# Current_Sensor.net
KiCad netlist of a schematic drawn in Altium Designer
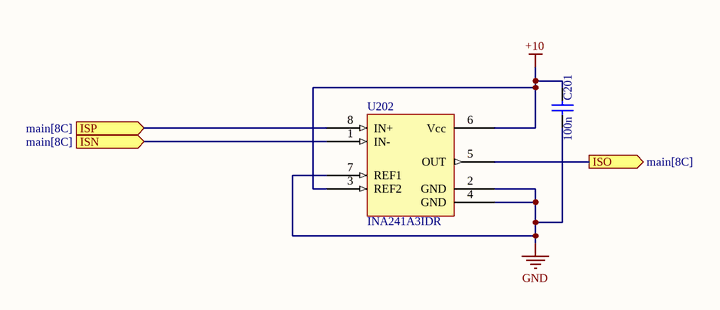
[diagram p0: Current_Sensor.SchDoc]

(export (version "E")
  (design (tool "Eeschema 10.0.6"))
  (components
    (comp (ref "C201")
      (value "100n")
      (footprint "CAP_1206")
      (description "Non Polarized Capacitor, SMD, 1206")
      (libsource (lib "Resistors and Capacitors") (part "CAPN 1206"))
    )
    (comp (ref "U202")
      (value "INA241A3IDR")
      (footprint "SOIC8_M")
      (description "Current Sense Amp")
      (libsource (lib "Projects_2025") (part "INA241A3IDR"))
    )
  )
  (nets
    (net (code "1") (name "+10") (class "Default")
      (node (ref "C201") (pin "2") (pinfunction "2_2") (pintype "passive"))
      (node (ref "U202") (pin "3") (pinfunction "REF2_3") (pintype "input"))
      (node (ref "U202") (pin "6") (pinfunction "Vcc_6") (pintype "power_in"))
    )
    (net (code "2") (name "/ISN") (class "Default")
      (node (ref "U202") (pin "1") (pinfunction "IN-_1") (pintype "input"))
    )
    (net (code "3") (name "/ISO") (class "Default")
      (node (ref "U202") (pin "5") (pinfunction "OUT_5") (pintype "output"))
    )
    (net (code "4") (name "/ISP") (class "Default")
      (node (ref "U202") (pin "8") (pinfunction "IN+_8") (pintype "input"))
    )
    (net (code "5") (name "GND") (class "Default")
      (node (ref "C201") (pin "1") (pinfunction "1_1") (pintype "passive"))
      (node (ref "U202") (pin "2") (pinfunction "GND_2") (pintype "power_in"))
      (node (ref "U202") (pin "4") (pinfunction "GND_4") (pintype "passive"))
      (node (ref "U202") (pin "7") (pinfunction "REF1_7") (pintype "input"))
    )
  )
)
